# pro_event_light_a_mkI_modules.net
KiCad netlist of a schematic drawn in EAGLE
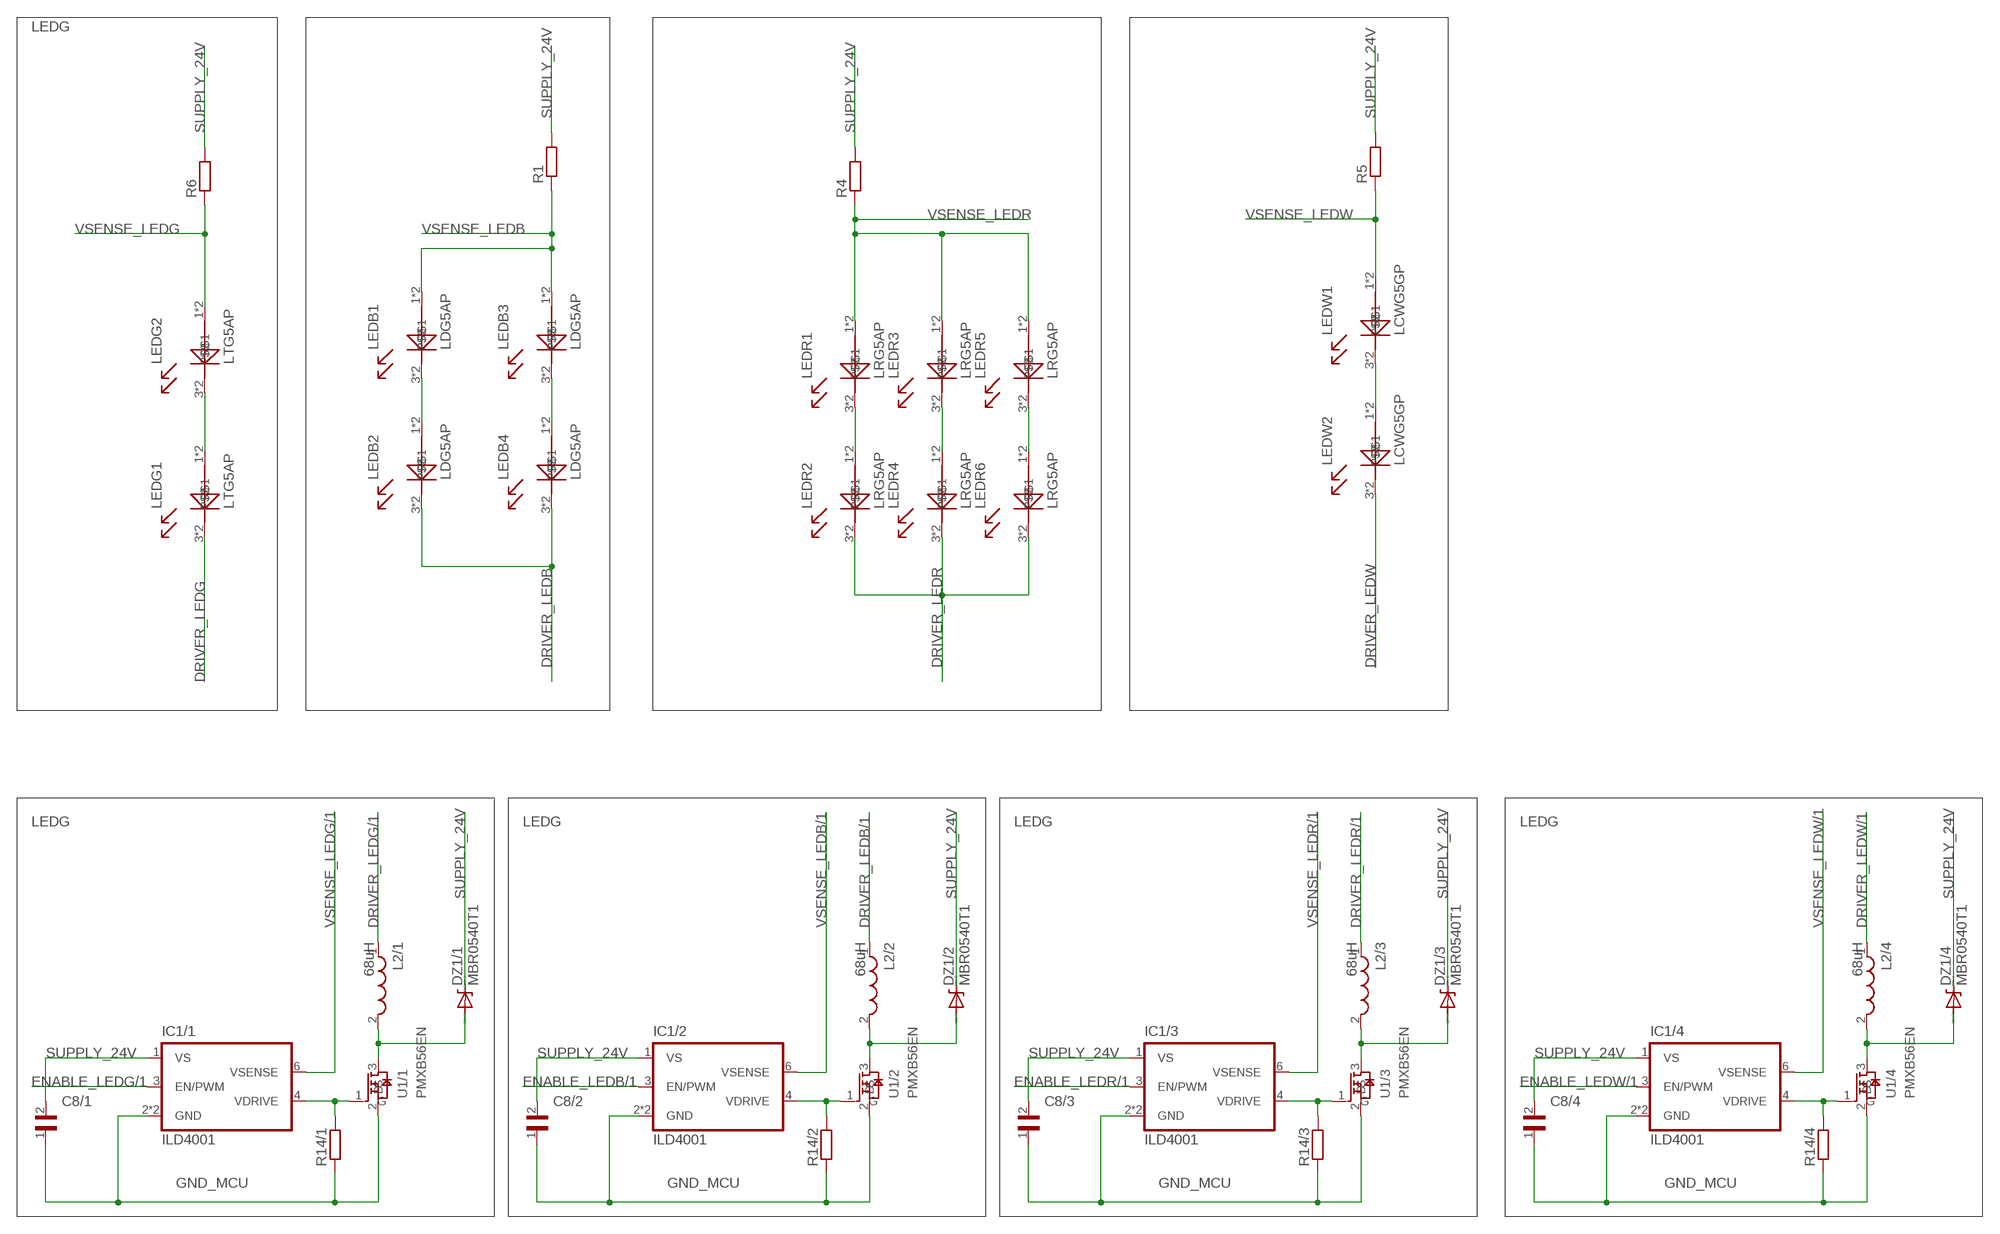
[diagram p0: schematic, sheet 1]

(export (version "E")
  (design (tool "Eeschema 10.0.6"))
  (components
    (comp (ref "C8/1")
      (value "WCAP-CSGP_0603-WAVE")
      (footprint "eagle-import:WCAP-CSGP_0603_WAVE")
      (libsource (lib "eagle-import") (part "WCAP-CSGP_0603-WAVE"))
    )
    (comp (ref "C8/2")
      (value "WCAP-CSGP_0603-WAVE")
      (footprint "eagle-import:WCAP-CSGP_0603_WAVE")
      (libsource (lib "eagle-import") (part "WCAP-CSGP_0603-WAVE"))
    )
    (comp (ref "C8/3")
      (value "WCAP-CSGP_0603-WAVE")
      (footprint "eagle-import:WCAP-CSGP_0603_WAVE")
      (libsource (lib "eagle-import") (part "WCAP-CSGP_0603-WAVE"))
    )
    (comp (ref "C8/4")
      (value "WCAP-CSGP_0603-WAVE")
      (footprint "eagle-import:WCAP-CSGP_0603_WAVE")
      (libsource (lib "eagle-import") (part "WCAP-CSGP_0603-WAVE"))
    )
    (comp (ref "DZ1/1")
      (value "MBR0540T1")
      (footprint "eagle-import:SOD123")
      (libsource (lib "eagle-import") (part "MBR0540T1"))
    )
    (comp (ref "DZ1/2")
      (value "MBR0540T1")
      (footprint "eagle-import:SOD123")
      (libsource (lib "eagle-import") (part "MBR0540T1"))
    )
    (comp (ref "DZ1/3")
      (value "MBR0540T1")
      (footprint "eagle-import:SOD123")
      (libsource (lib "eagle-import") (part "MBR0540T1"))
    )
    (comp (ref "DZ1/4")
      (value "MBR0540T1")
      (footprint "eagle-import:SOD123")
      (libsource (lib "eagle-import") (part "MBR0540T1"))
    )
    (comp (ref "IC1/1")
      (value "ILD4001")
      (footprint "eagle-import:SC74_INFINEON")
      (libsource (lib "eagle-import") (part "ILD4001"))
    )
    (comp (ref "IC1/2")
      (value "ILD4001")
      (footprint "eagle-import:SC74_INFINEON")
      (libsource (lib "eagle-import") (part "ILD4001"))
    )
    (comp (ref "IC1/3")
      (value "ILD4001")
      (footprint "eagle-import:SC74_INFINEON")
      (libsource (lib "eagle-import") (part "ILD4001"))
    )
    (comp (ref "IC1/4")
      (value "ILD4001")
      (footprint "eagle-import:SC74_INFINEON")
      (libsource (lib "eagle-import") (part "ILD4001"))
    )
    (comp (ref "L2/1")
      (value "68uH")
      (footprint "eagle-import:WE-LQ_M")
      (libsource (lib "eagle-import") (part "WE-LQ_1210"))
    )
    (comp (ref "L2/2")
      (value "68uH")
      (footprint "eagle-import:WE-LQ_M")
      (libsource (lib "eagle-import") (part "WE-LQ_1210"))
    )
    (comp (ref "L2/3")
      (value "68uH")
      (footprint "eagle-import:WE-LQ_M")
      (libsource (lib "eagle-import") (part "WE-LQ_1210"))
    )
    (comp (ref "L2/4")
      (value "68uH")
      (footprint "eagle-import:WE-LQ_M")
      (libsource (lib "eagle-import") (part "WE-LQ_1210"))
    )
    (comp (ref "LEDB1")
      (value "LDG5AP")
      (footprint "eagle-import:P-LCC-2")
      (libsource (lib "eagle-import") (part "LDG5AP"))
    )
    (comp (ref "LEDB2")
      (value "LDG5AP")
      (footprint "eagle-import:P-LCC-2")
      (libsource (lib "eagle-import") (part "LDG5AP"))
    )
    (comp (ref "LEDB3")
      (value "LDG5AP")
      (footprint "eagle-import:P-LCC-2")
      (libsource (lib "eagle-import") (part "LDG5AP"))
    )
    (comp (ref "LEDB4")
      (value "LDG5AP")
      (footprint "eagle-import:P-LCC-2")
      (libsource (lib "eagle-import") (part "LDG5AP"))
    )
    (comp (ref "LEDG1")
      (value "LTG5AP")
      (footprint "eagle-import:P-LCC-2")
      (libsource (lib "eagle-import") (part "LTG5AP"))
    )
    (comp (ref "LEDG2")
      (value "LTG5AP")
      (footprint "eagle-import:P-LCC-2")
      (libsource (lib "eagle-import") (part "LTG5AP"))
    )
    (comp (ref "LEDR1")
      (value "LRG5AP")
      (footprint "eagle-import:P-LCC-2")
      (libsource (lib "eagle-import") (part "LRG5AP"))
    )
    (comp (ref "LEDR2")
      (value "LRG5AP")
      (footprint "eagle-import:P-LCC-2")
      (libsource (lib "eagle-import") (part "LRG5AP"))
    )
    (comp (ref "LEDR3")
      (value "LRG5AP")
      (footprint "eagle-import:P-LCC-2")
      (libsource (lib "eagle-import") (part "LRG5AP"))
    )
    (comp (ref "LEDR4")
      (value "LRG5AP")
      (footprint "eagle-import:P-LCC-2")
      (libsource (lib "eagle-import") (part "LRG5AP"))
    )
    (comp (ref "LEDR5")
      (value "LRG5AP")
      (footprint "eagle-import:P-LCC-2")
      (libsource (lib "eagle-import") (part "LRG5AP"))
    )
    (comp (ref "LEDR6")
      (value "LRG5AP")
      (footprint "eagle-import:P-LCC-2")
      (libsource (lib "eagle-import") (part "LRG5AP"))
    )
    (comp (ref "LEDW1")
      (value "LCWG5GP")
      (footprint "eagle-import:P-LCC-2")
      (libsource (lib "eagle-import") (part "LCWG5GP"))
    )
    (comp (ref "LEDW2")
      (value "LCWG5GP")
      (footprint "eagle-import:P-LCC-2")
      (libsource (lib "eagle-import") (part "LCWG5GP"))
    )
    (comp (ref "R1")
      (value "R-EU_R0603")
      (footprint "eagle-import:R0603")
      (libsource (lib "eagle-import") (part "R-EU_R0603"))
    )
    (comp (ref "R4")
      (value "R-EU_R0603")
      (footprint "eagle-import:R0603")
      (libsource (lib "eagle-import") (part "R-EU_R0603"))
    )
    (comp (ref "R5")
      (value "R-EU_R0603")
      (footprint "eagle-import:R0603")
      (libsource (lib "eagle-import") (part "R-EU_R0603"))
    )
    (comp (ref "R6")
      (value "R-EU_R0603")
      (footprint "eagle-import:R0603")
      (libsource (lib "eagle-import") (part "R-EU_R0603"))
    )
    (comp (ref "R14/1")
      (value "R-EU_R0603")
      (footprint "eagle-import:R0603")
      (libsource (lib "eagle-import") (part "R-EU_R0603"))
    )
    (comp (ref "R14/2")
      (value "R-EU_R0603")
      (footprint "eagle-import:R0603")
      (libsource (lib "eagle-import") (part "R-EU_R0603"))
    )
    (comp (ref "R14/3")
      (value "R-EU_R0603")
      (footprint "eagle-import:R0603")
      (libsource (lib "eagle-import") (part "R-EU_R0603"))
    )
    (comp (ref "R14/4")
      (value "R-EU_R0603")
      (footprint "eagle-import:R0603")
      (libsource (lib "eagle-import") (part "R-EU_R0603"))
    )
    (comp (ref "U1/1")
      (value "PMXB56EN")
      (footprint "eagle-import:DFN1010D-3")
      (libsource (lib "eagle-import") (part "PMXB56EN"))
    )
    (comp (ref "U1/2")
      (value "PMXB56EN")
      (footprint "eagle-import:DFN1010D-3")
      (libsource (lib "eagle-import") (part "PMXB56EN"))
    )
    (comp (ref "U1/3")
      (value "PMXB56EN")
      (footprint "eagle-import:DFN1010D-3")
      (libsource (lib "eagle-import") (part "PMXB56EN"))
    )
    (comp (ref "U1/4")
      (value "PMXB56EN")
      (footprint "eagle-import:DFN1010D-3")
      (libsource (lib "eagle-import") (part "PMXB56EN"))
    )
  )
  (nets
    (net (code "1") (name "/DRIVER_LEDB") (class "Default")
      (node (ref "LEDB2") (pin "3") (pinfunction "P$2_3") (pintype "bidirectional"))
      (node (ref "LEDB2") (pin "4") (pinfunction "P$2_4") (pintype "bidirectional"))
      (node (ref "LEDB4") (pin "3") (pinfunction "P$2_3") (pintype "bidirectional"))
      (node (ref "LEDB4") (pin "4") (pinfunction "P$2_4") (pintype "bidirectional"))
    )
    (net (code "2") (name "/DRIVER_LEDB{slash}1") (class "Default")
      (node (ref "L2/2") (pin "1") (pinfunction "1_1") (pintype "passive"))
    )
    (net (code "3") (name "/DRIVER_LEDG") (class "Default")
      (node (ref "LEDG1") (pin "3") (pinfunction "P$2_3") (pintype "bidirectional"))
      (node (ref "LEDG1") (pin "4") (pinfunction "P$2_4") (pintype "bidirectional"))
    )
    (net (code "4") (name "/DRIVER_LEDG{slash}1") (class "Default")
      (node (ref "L2/1") (pin "1") (pinfunction "1_1") (pintype "passive"))
    )
    (net (code "5") (name "/DRIVER_LEDR") (class "Default")
      (node (ref "LEDR2") (pin "3") (pinfunction "P$2_3") (pintype "bidirectional"))
      (node (ref "LEDR2") (pin "4") (pinfunction "P$2_4") (pintype "bidirectional"))
      (node (ref "LEDR4") (pin "3") (pinfunction "P$2_3") (pintype "bidirectional"))
      (node (ref "LEDR4") (pin "4") (pinfunction "P$2_4") (pintype "bidirectional"))
      (node (ref "LEDR6") (pin "3") (pinfunction "P$2_3") (pintype "bidirectional"))
      (node (ref "LEDR6") (pin "4") (pinfunction "P$2_4") (pintype "bidirectional"))
    )
    (net (code "6") (name "/DRIVER_LEDR{slash}1") (class "Default")
      (node (ref "L2/3") (pin "1") (pinfunction "1_1") (pintype "passive"))
    )
    (net (code "7") (name "/DRIVER_LEDW") (class "Default")
      (node (ref "LEDW2") (pin "3") (pinfunction "P$2_3") (pintype "bidirectional"))
      (node (ref "LEDW2") (pin "4") (pinfunction "P$2_4") (pintype "bidirectional"))
    )
    (net (code "8") (name "/DRIVER_LEDW{slash}1") (class "Default")
      (node (ref "L2/4") (pin "1") (pinfunction "1_1") (pintype "passive"))
    )
    (net (code "9") (name "/ENABLE_LEDB{slash}1") (class "Default")
      (node (ref "IC1/2") (pin "3") (pinfunction "EN/PWM_3") (pintype "input"))
    )
    (net (code "10") (name "/ENABLE_LEDG{slash}1") (class "Default")
      (node (ref "IC1/1") (pin "3") (pinfunction "EN/PWM_3") (pintype "input"))
    )
    (net (code "11") (name "/ENABLE_LEDR{slash}1") (class "Default")
      (node (ref "IC1/3") (pin "3") (pinfunction "EN/PWM_3") (pintype "input"))
    )
    (net (code "12") (name "/ENABLE_LEDW{slash}1") (class "Default")
      (node (ref "IC1/4") (pin "3") (pinfunction "EN/PWM_3") (pintype "input"))
    )
    (net (code "13") (name "/GND_MCU") (class "Default")
      (node (ref "C8/1") (pin "1") (pinfunction "1_1") (pintype "passive"))
      (node (ref "C8/2") (pin "1") (pinfunction "1_1") (pintype "passive"))
      (node (ref "C8/3") (pin "1") (pinfunction "1_1") (pintype "passive"))
      (node (ref "C8/4") (pin "1") (pinfunction "1_1") (pintype "passive"))
      (node (ref "IC1/1") (pin "2") (pinfunction "GND_2") (pintype "power_in"))
      (node (ref "IC1/1") (pin "5") (pinfunction "GND_5") (pintype "power_in"))
      (node (ref "IC1/2") (pin "2") (pinfunction "GND_2") (pintype "power_in"))
      (node (ref "IC1/2") (pin "5") (pinfunction "GND_5") (pintype "power_in"))
      (node (ref "IC1/3") (pin "2") (pinfunction "GND_2") (pintype "power_in"))
      (node (ref "IC1/3") (pin "5") (pinfunction "GND_5") (pintype "power_in"))
      (node (ref "IC1/4") (pin "2") (pinfunction "GND_2") (pintype "power_in"))
      (node (ref "IC1/4") (pin "5") (pinfunction "GND_5") (pintype "power_in"))
      (node (ref "R14/1") (pin "1") (pinfunction "1_1") (pintype "passive"))
      (node (ref "R14/2") (pin "1") (pinfunction "1_1") (pintype "passive"))
      (node (ref "R14/3") (pin "1") (pinfunction "1_1") (pintype "passive"))
      (node (ref "R14/4") (pin "1") (pinfunction "1_1") (pintype "passive"))
      (node (ref "U1/1") (pin "2") (pinfunction "S_2") (pintype "bidirectional"))
      (node (ref "U1/2") (pin "2") (pinfunction "S_2") (pintype "bidirectional"))
      (node (ref "U1/3") (pin "2") (pinfunction "S_2") (pintype "bidirectional"))
      (node (ref "U1/4") (pin "2") (pinfunction "S_2") (pintype "bidirectional"))
    )
    (net (code "14") (name "/SUPPLY_24V") (class "Default")
      (node (ref "C8/1") (pin "2") (pinfunction "2_2") (pintype "passive"))
      (node (ref "C8/2") (pin "2") (pinfunction "2_2") (pintype "passive"))
      (node (ref "C8/3") (pin "2") (pinfunction "2_2") (pintype "passive"))
      (node (ref "C8/4") (pin "2") (pinfunction "2_2") (pintype "passive"))
      (node (ref "DZ1/1") (pin "C") (pinfunction "C_C") (pintype "passive"))
      (node (ref "DZ1/2") (pin "C") (pinfunction "C_C") (pintype "passive"))
      (node (ref "DZ1/3") (pin "C") (pinfunction "C_C") (pintype "passive"))
      (node (ref "DZ1/4") (pin "C") (pinfunction "C_C") (pintype "passive"))
      (node (ref "IC1/1") (pin "1") (pinfunction "VS_1") (pintype "input"))
      (node (ref "IC1/2") (pin "1") (pinfunction "VS_1") (pintype "input"))
      (node (ref "IC1/3") (pin "1") (pinfunction "VS_1") (pintype "input"))
      (node (ref "IC1/4") (pin "1") (pinfunction "VS_1") (pintype "input"))
      (node (ref "R1") (pin "2") (pinfunction "2_2") (pintype "passive"))
      (node (ref "R4") (pin "2") (pinfunction "2_2") (pintype "passive"))
      (node (ref "R5") (pin "2") (pinfunction "2_2") (pintype "passive"))
      (node (ref "R6") (pin "2") (pinfunction "2_2") (pintype "passive"))
    )
    (net (code "15") (name "/VSENSE_LEDB") (class "Default")
      (node (ref "LEDB1") (pin "1") (pinfunction "P$1_1") (pintype "bidirectional"))
      (node (ref "LEDB1") (pin "2") (pinfunction "P$1_2") (pintype "bidirectional"))
      (node (ref "LEDB3") (pin "1") (pinfunction "P$1_1") (pintype "bidirectional"))
      (node (ref "LEDB3") (pin "2") (pinfunction "P$1_2") (pintype "bidirectional"))
      (node (ref "R1") (pin "1") (pinfunction "1_1") (pintype "passive"))
    )
    (net (code "16") (name "/VSENSE_LEDB{slash}1") (class "Default")
      (node (ref "IC1/2") (pin "6") (pinfunction "VSENSE_6") (pintype "input"))
    )
    (net (code "17") (name "/VSENSE_LEDG") (class "Default")
      (node (ref "LEDG2") (pin "1") (pinfunction "P$1_1") (pintype "bidirectional"))
      (node (ref "LEDG2") (pin "2") (pinfunction "P$1_2") (pintype "bidirectional"))
      (node (ref "R6") (pin "1") (pinfunction "1_1") (pintype "passive"))
    )
    (net (code "18") (name "/VSENSE_LEDG{slash}1") (class "Default")
      (node (ref "IC1/1") (pin "6") (pinfunction "VSENSE_6") (pintype "input"))
    )
    (net (code "19") (name "/VSENSE_LEDR") (class "Default")
      (node (ref "LEDR1") (pin "1") (pinfunction "P$1_1") (pintype "bidirectional"))
      (node (ref "LEDR1") (pin "2") (pinfunction "P$1_2") (pintype "bidirectional"))
      (node (ref "LEDR3") (pin "1") (pinfunction "P$1_1") (pintype "bidirectional"))
      (node (ref "LEDR3") (pin "2") (pinfunction "P$1_2") (pintype "bidirectional"))
      (node (ref "LEDR5") (pin "1") (pinfunction "P$1_1") (pintype "bidirectional"))
      (node (ref "LEDR5") (pin "2") (pinfunction "P$1_2") (pintype "bidirectional"))
      (node (ref "R4") (pin "1") (pinfunction "1_1") (pintype "passive"))
    )
    (net (code "20") (name "/VSENSE_LEDR{slash}1") (class "Default")
      (node (ref "IC1/3") (pin "6") (pinfunction "VSENSE_6") (pintype "input"))
    )
    (net (code "21") (name "/VSENSE_LEDW") (class "Default")
      (node (ref "LEDW1") (pin "1") (pinfunction "P$1_1") (pintype "bidirectional"))
      (node (ref "LEDW1") (pin "2") (pinfunction "P$1_2") (pintype "bidirectional"))
      (node (ref "R5") (pin "1") (pinfunction "1_1") (pintype "passive"))
    )
    (net (code "22") (name "/VSENSE_LEDW{slash}1") (class "Default")
      (node (ref "IC1/4") (pin "6") (pinfunction "VSENSE_6") (pintype "input"))
    )
    (net (code "23") (name "Net-(IC1/1-VDRIVE)") (class "Default")
      (node (ref "IC1/1") (pin "4") (pinfunction "VDRIVE_4") (pintype "output"))
      (node (ref "R14/1") (pin "2") (pinfunction "2_2") (pintype "passive"))
      (node (ref "U1/1") (pin "1") (pinfunction "G_1") (pintype "bidirectional"))
    )
    (net (code "24") (name "Net-(IC1/2-VDRIVE)") (class "Default")
      (node (ref "IC1/2") (pin "4") (pinfunction "VDRIVE_4") (pintype "output"))
      (node (ref "R14/2") (pin "2") (pinfunction "2_2") (pintype "passive"))
      (node (ref "U1/2") (pin "1") (pinfunction "G_1") (pintype "bidirectional"))
    )
    (net (code "25") (name "Net-(IC1/3-VDRIVE)") (class "Default")
      (node (ref "IC1/3") (pin "4") (pinfunction "VDRIVE_4") (pintype "output"))
      (node (ref "R14/3") (pin "2") (pinfunction "2_2") (pintype "passive"))
      (node (ref "U1/3") (pin "1") (pinfunction "G_1") (pintype "bidirectional"))
    )
    (net (code "26") (name "Net-(IC1/4-VDRIVE)") (class "Default")
      (node (ref "IC1/4") (pin "4") (pinfunction "VDRIVE_4") (pintype "output"))
      (node (ref "R14/4") (pin "2") (pinfunction "2_2") (pintype "passive"))
      (node (ref "U1/4") (pin "1") (pinfunction "G_1") (pintype "bidirectional"))
    )
    (net (code "27") (name "Net-(LEDB1-P$2-Pad3)") (class "Default")
      (node (ref "LEDB1") (pin "3") (pinfunction "P$2_3") (pintype "bidirectional"))
      (node (ref "LEDB1") (pin "4") (pinfunction "P$2_4") (pintype "bidirectional"))
      (node (ref "LEDB2") (pin "1") (pinfunction "P$1_1") (pintype "bidirectional"))
      (node (ref "LEDB2") (pin "2") (pinfunction "P$1_2") (pintype "bidirectional"))
    )
    (net (code "28") (name "Net-(LEDB3-P$2-Pad3)") (class "Default")
      (node (ref "LEDB3") (pin "3") (pinfunction "P$2_3") (pintype "bidirectional"))
      (node (ref "LEDB3") (pin "4") (pinfunction "P$2_4") (pintype "bidirectional"))
      (node (ref "LEDB4") (pin "1") (pinfunction "P$1_1") (pintype "bidirectional"))
      (node (ref "LEDB4") (pin "2") (pinfunction "P$1_2") (pintype "bidirectional"))
    )
    (net (code "29") (name "Net-(LEDG1-P$1-Pad1)") (class "Default")
      (node (ref "LEDG1") (pin "1") (pinfunction "P$1_1") (pintype "bidirectional"))
      (node (ref "LEDG1") (pin "2") (pinfunction "P$1_2") (pintype "bidirectional"))
      (node (ref "LEDG2") (pin "3") (pinfunction "P$2_3") (pintype "bidirectional"))
      (node (ref "LEDG2") (pin "4") (pinfunction "P$2_4") (pintype "bidirectional"))
    )
    (net (code "30") (name "Net-(LEDR1-P$2-Pad3)") (class "Default")
      (node (ref "LEDR1") (pin "3") (pinfunction "P$2_3") (pintype "bidirectional"))
      (node (ref "LEDR1") (pin "4") (pinfunction "P$2_4") (pintype "bidirectional"))
      (node (ref "LEDR2") (pin "1") (pinfunction "P$1_1") (pintype "bidirectional"))
      (node (ref "LEDR2") (pin "2") (pinfunction "P$1_2") (pintype "bidirectional"))
    )
    (net (code "31") (name "Net-(LEDR3-P$2-Pad3)") (class "Default")
      (node (ref "LEDR3") (pin "3") (pinfunction "P$2_3") (pintype "bidirectional"))
      (node (ref "LEDR3") (pin "4") (pinfunction "P$2_4") (pintype "bidirectional"))
      (node (ref "LEDR4") (pin "1") (pinfunction "P$1_1") (pintype "bidirectional"))
      (node (ref "LEDR4") (pin "2") (pinfunction "P$1_2") (pintype "bidirectional"))
    )
    (net (code "32") (name "Net-(LEDR5-P$2-Pad3)") (class "Default")
      (node (ref "LEDR5") (pin "3") (pinfunction "P$2_3") (pintype "bidirectional"))
      (node (ref "LEDR5") (pin "4") (pinfunction "P$2_4") (pintype "bidirectional"))
      (node (ref "LEDR6") (pin "1") (pinfunction "P$1_1") (pintype "bidirectional"))
      (node (ref "LEDR6") (pin "2") (pinfunction "P$1_2") (pintype "bidirectional"))
    )
    (net (code "33") (name "Net-(LEDW1-P$2-Pad3)") (class "Default")
      (node (ref "LEDW1") (pin "3") (pinfunction "P$2_3") (pintype "bidirectional"))
      (node (ref "LEDW1") (pin "4") (pinfunction "P$2_4") (pintype "bidirectional"))
      (node (ref "LEDW2") (pin "1") (pinfunction "P$1_1") (pintype "bidirectional"))
      (node (ref "LEDW2") (pin "2") (pinfunction "P$1_2") (pintype "bidirectional"))
    )
    (net (code "34") (name "Net-(U1/1-D)") (class "Default")
      (node (ref "DZ1/1") (pin "A") (pinfunction "A_A") (pintype "passive"))
      (node (ref "L2/1") (pin "2") (pinfunction "2_2") (pintype "passive"))
      (node (ref "U1/1") (pin "3") (pinfunction "D_3") (pintype "bidirectional"))
    )
    (net (code "35") (name "Net-(U1/2-D)") (class "Default")
      (node (ref "DZ1/2") (pin "A") (pinfunction "A_A") (pintype "passive"))
      (node (ref "L2/2") (pin "2") (pinfunction "2_2") (pintype "passive"))
      (node (ref "U1/2") (pin "3") (pinfunction "D_3") (pintype "bidirectional"))
    )
    (net (code "36") (name "Net-(U1/3-D)") (class "Default")
      (node (ref "DZ1/3") (pin "A") (pinfunction "A_A") (pintype "passive"))
      (node (ref "L2/3") (pin "2") (pinfunction "2_2") (pintype "passive"))
      (node (ref "U1/3") (pin "3") (pinfunction "D_3") (pintype "bidirectional"))
    )
    (net (code "37") (name "Net-(U1/4-D)") (class "Default")
      (node (ref "DZ1/4") (pin "A") (pinfunction "A_A") (pintype "passive"))
      (node (ref "L2/4") (pin "2") (pinfunction "2_2") (pintype "passive"))
      (node (ref "U1/4") (pin "3") (pinfunction "D_3") (pintype "bidirectional"))
    )
  )
)
